# nRF5340.net
KiCad netlist of a schematic drawn in Altium Designer
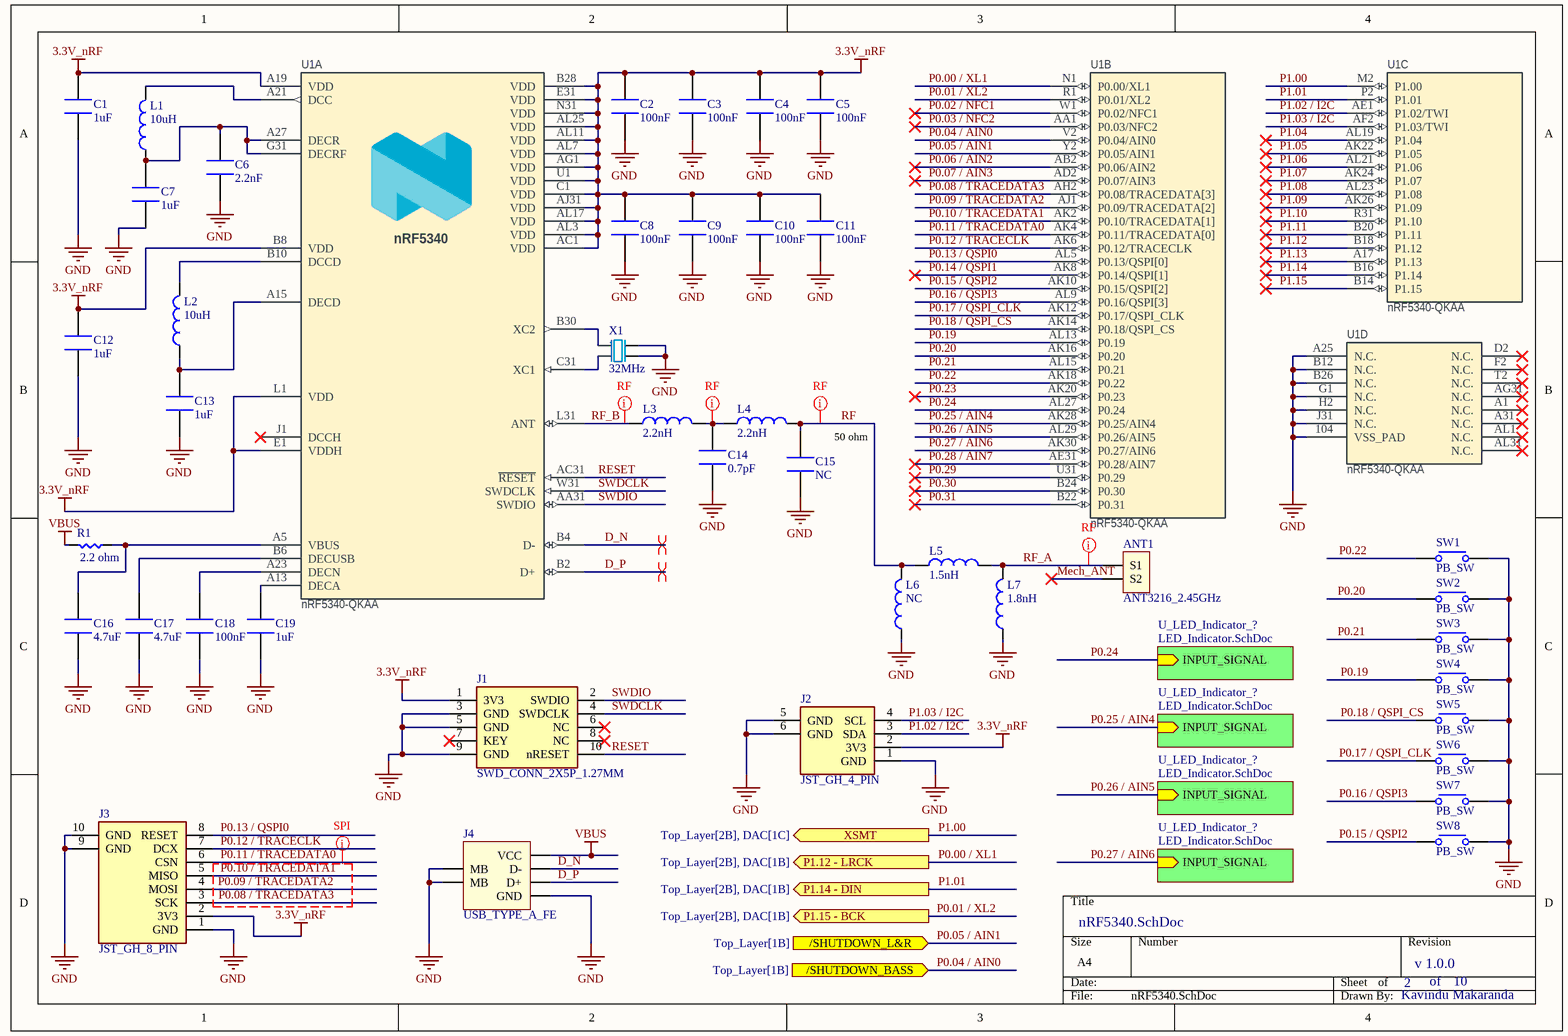
[diagram p0: nRF5340.SchDoc]

(export (version "E")
  (design (tool "Eeschema 10.0.6"))
  (components
    (comp (ref "ANT1")
      (value "ANT3216_2.45GHz")
      (footprint "ANT3216_2.4GHz")
      (libsource (lib "Schlib1") (part "ANT3216_2.45GHz"))
    )
    (comp (ref "C1")
      (value "1uF")
      (footprint "CAPC0402X06N")
      (description "C307427, CL05B105KQ5NQNC, 1uF 6.3V X7R ±10% 0402 Multilayer Ceramic Capacitors MLCC - SMD/SMT ROHS")
      (libsource (lib "Schlib1") (part "CC0402_1uF_X7R"))
    )
    (comp (ref "C2")
      (value "100nF")
      (footprint "CAPC0201X03N")
      (libsource (lib "Schlib1") (part "CC0201_100nF_X7R"))
    )
    (comp (ref "C3")
      (value "100nF")
      (footprint "CAPC0201X03N")
      (libsource (lib "Schlib1") (part "CC0201_100nF_X7R"))
    )
    (comp (ref "C4")
      (value "100nF")
      (footprint "CAPC0201X03N")
      (libsource (lib "Schlib1") (part "CC0201_100nF_X7R"))
    )
    (comp (ref "C5")
      (value "100nF")
      (footprint "CAPC0201X03N")
      (libsource (lib "Schlib1") (part "CC0201_100nF_X7R"))
    )
    (comp (ref "C6")
      (value "2.2nF")
      (footprint "CAPC0201X03N")
      (libsource (lib "Schlib1") (part "CC0201_2.2nF_X7R"))
    )
    (comp (ref "C7")
      (value "1uF")
      (footprint "CAPC0402X06N")
      (description "C307427, CL05B105KQ5NQNC, 1uF 6.3V X7R ±10% 0402 Multilayer Ceramic Capacitors MLCC - SMD/SMT ROHS")
      (libsource (lib "Schlib1") (part "CC0402_1uF_X7R"))
    )
    (comp (ref "C8")
      (value "100nF")
      (footprint "CAPC0201X03N")
      (libsource (lib "Schlib1") (part "CC0201_100nF_X7R"))
    )
    (comp (ref "C9")
      (value "100nF")
      (footprint "CAPC0201X03N")
      (libsource (lib "Schlib1") (part "CC0201_100nF_X7R"))
    )
    (comp (ref "C10")
      (value "100nF")
      (footprint "CAPC0201X03N")
      (libsource (lib "Schlib1") (part "CC0201_100nF_X7R"))
    )
    (comp (ref "C11")
      (value "100nF")
      (footprint "CAPC0201X03N")
      (libsource (lib "Schlib1") (part "CC0201_100nF_X7R"))
    )
    (comp (ref "C12")
      (value "1uF")
      (footprint "CAPC0402X06N")
      (description "C307427, CL05B105KQ5NQNC, 1uF 6.3V X7R ±10% 0402 Multilayer Ceramic Capacitors MLCC - SMD/SMT ROHS")
      (libsource (lib "Schlib1") (part "CC0402_1uF_X7R"))
    )
    (comp (ref "C13")
      (value "1uF")
      (footprint "CAPC0402X06N")
      (description "C307427, CL05B105KQ5NQNC, 1uF 6.3V X7R ±10% 0402 Multilayer Ceramic Capacitors MLCC - SMD/SMT ROHS")
      (libsource (lib "Schlib1") (part "CC0402_1uF_X7R"))
    )
    (comp (ref "C14")
      (value "0.7pF")
      (footprint "CAPC0201X03N")
      (description "C907945, GJM0335C1ER70WB01D, 0.7pF 25V C0G 0201 Multilayer Ceramic Capacitors MLCC - SMD/SMT ROHS")
      (libsource (lib "Schlib1") (part "CC0201_0.7pF_COG"))
    )
    (comp (ref "C15")
      (value "NC")
      (footprint "CAPC0201X03N")
      (description "C907945, GJM0335C1ER70WB01D, 0.7pF 25V C0G 0201 Multilayer Ceramic Capacitors MLCC - SMD/SMT ROHS")
      (libsource (lib "Schlib1") (part "CC0201_0.7pF_COG"))
    )
    (comp (ref "C16")
      (value "4.7uF")
      (footprint "CAP0805X13N")
      (libsource (lib "Schlib1") (part "CC0805_4.7uF_X7R"))
    )
    (comp (ref "C17")
      (value "4.7uF")
      (footprint "CAP0805X13N")
      (libsource (lib "Schlib1") (part "CC0805_4.7uF_X7R"))
    )
    (comp (ref "C18")
      (value "100nF")
      (footprint "CAPC0201X03N")
      (libsource (lib "Schlib1") (part "CC0201_100nF_X7R"))
    )
    (comp (ref "C19")
      (value "1uF")
      (footprint "CAPC0402X06N")
      (description "C307427, CL05B105KQ5NQNC, 1uF 6.3V X7R ±10% 0402 Multilayer Ceramic Capacitors MLCC - SMD/SMT ROHS")
      (libsource (lib "Schlib1") (part "CC0402_1uF_X7R"))
    )
    (comp (ref "J1")
      (value "SWD_CONN_2X5P_1.27MM")
      (footprint "CONN_2X5P_1.27MM - duplicate")
      (libsource (lib "Schlib1") (part "SWD_CONN_2X5P_1.27MM"))
    )
    (comp (ref "J2")
      (value "JST_GH_4_PIN")
      (footprint "JST_GH_4_PIN")
      (libsource (lib "Schlib1") (part "JST_GH_4_PIN"))
    )
    (comp (ref "J3")
      (value "JST_GH_8_PIN")
      (footprint "JST_GH_8_PIN")
      (libsource (lib "Schlib1") (part "JST_GH_8_PIN"))
    )
    (comp (ref "J4")
      (value "USB_TYPE_A_FE")
      (footprint "USB_TYPE_A_FE")
      (libsource (lib "Schlib1") (part "USB_TYPE_A_FE"))
    )
    (comp (ref "L1")
      (value "10uH")
      (footprint "INDC0603X08N")
      (libsource (lib "Schlib1") (part "IN0603_10uH"))
    )
    (comp (ref "L2")
      (value "10uH")
      (footprint "INDC0603X08N")
      (libsource (lib "Schlib1") (part "IN0603_10uH"))
    )
    (comp (ref "L3") (value "2.2nH") (footprint "INDC0201") (libsource (lib "Schlib1") (part "IN0201_2.2nH")))
    (comp (ref "L4") (value "2.2nH") (footprint "INDC0201") (libsource (lib "Schlib1") (part "IN0201_2.2nH")))
    (comp (ref "L5") (value "1.5nH") (footprint "INDC0201") (libsource (lib "Schlib1") (part "IN0201_1.5nH")))
    (comp (ref "L6") (value "NC") (footprint "INDC0201") (libsource (lib "Schlib1") (part "IN0201_1.8nH")))
    (comp (ref "L7") (value "1.8nH") (footprint "INDC0201") (libsource (lib "Schlib1") (part "IN0201_1.8nH")))
    (comp (ref "R1")
      (value "2.2 ohm")
      (footprint "CAPC0201X03N")
      (libsource (lib "Schlib1") (part "REC0201_2.2_THICK"))
    )
    (comp (ref "SW1") (value "PB_SW") (footprint "SW_PB_2") (libsource (lib "Schlib1") (part "SW_SMD_PUSH")))
    (comp (ref "SW2") (value "PB_SW") (footprint "SW_PB_2") (libsource (lib "Schlib1") (part "SW_SMD_PUSH")))
    (comp (ref "SW3") (value "PB_SW") (footprint "SW_PB_2") (libsource (lib "Schlib1") (part "SW_SMD_PUSH")))
    (comp (ref "SW4") (value "PB_SW") (footprint "SW_PB_2") (libsource (lib "Schlib1") (part "SW_SMD_PUSH")))
    (comp (ref "SW5") (value "PB_SW") (footprint "SW_PB_2") (libsource (lib "Schlib1") (part "SW_SMD_PUSH")))
    (comp (ref "SW6") (value "PB_SW") (footprint "SW_PB_2") (libsource (lib "Schlib1") (part "SW_SMD_PUSH")))
    (comp (ref "SW7") (value "PB_SW") (footprint "SW_PB_2") (libsource (lib "Schlib1") (part "SW_SMD_PUSH")))
    (comp (ref "SW8") (value "PB_SW") (footprint "SW_PB_2") (libsource (lib "Schlib1") (part "SW_SMD_PUSH")))
    (comp (ref "U1")
      (value "nRF5340-QKAA")
      (footprint "AQFN40P700X700X85_HS-99N")
      (description "Multi-protocol Bluetooth Low Energy, IEEE 802.15.4, ANT and 2.4GHz proprietary system-on-chip")
      (libsource (lib "nRF5340_qkaa_config4") (part "nRF5340-QKAA"))
    )
    (comp (ref "X1")
      (value "32MHz")
      (footprint "CRYOSC_3.2X2.5M")
      (libsource (lib "Schlib1") (part "SMD3225_4P_32MHz_OSC"))
    )
  )
  (nets
    (net (code "1") (name "/D_N") (class "Default")
      (node (ref "J4") (pin "2") (pinfunction "D-_2") (pintype "passive"))
      (node (ref "U1") (pin "B4") (pinfunction "D-_B4") (pintype "bidirectional"))
    )
    (net (code "2") (name "/D_P") (class "Default")
      (node (ref "J4") (pin "3") (pinfunction "D+_3") (pintype "passive"))
      (node (ref "U1") (pin "B2") (pinfunction "D+_B2") (pintype "bidirectional"))
    )
    (net (code "3") (name "/Mech_ANT") (class "Default")
      (node (ref "ANT1") (pin "2") (pinfunction "S2_2") (pintype "passive+no_connect"))
    )
    (net (code "4") (name "/P0.00 {slash} XL1") (class "Default")
      (node (ref "U1") (pin "N1") (pinfunction "P0.00/XL1_N1") (pintype "bidirectional"))
    )
    (net (code "5") (name "/P0.01 {slash} XL2") (class "Default")
      (node (ref "U1") (pin "R1") (pinfunction "P0.01/XL2_R1") (pintype "bidirectional"))
    )
    (net (code "6") (name "/P0.02 {slash} NFC1") (class "Default")
      (node (ref "U1") (pin "W1") (pinfunction "P0.02/NFC1_W1") (pintype "bidirectional+no_connect"))
    )
    (net (code "7") (name "/P0.03 {slash} NFC2") (class "Default")
      (node (ref "U1") (pin "AA1") (pinfunction "P0.03/NFC2_AA1") (pintype "bidirectional+no_connect"))
    )
    (net (code "8") (name "/P0.04 {slash} AIN0") (class "Default")
      (node (ref "U1") (pin "V2") (pinfunction "P0.04/AIN0_V2") (pintype "bidirectional"))
    )
    (net (code "9") (name "/P0.05 {slash} AIN1") (class "Default")
      (node (ref "U1") (pin "Y2") (pinfunction "P0.05/AIN1_Y2") (pintype "bidirectional"))
    )
    (net (code "10") (name "/P0.06 {slash} AIN2") (class "Default")
      (node (ref "U1") (pin "AB2") (pinfunction "P0.06/AIN2_AB2") (pintype "bidirectional+no_connect"))
    )
    (net (code "11") (name "/P0.07 {slash} AIN3") (class "Default")
      (node (ref "U1") (pin "AD2") (pinfunction "P0.07/AIN3_AD2") (pintype "bidirectional+no_connect"))
    )
    (net (code "12") (name "/P0.08 {slash} TRACEDATA3") (class "Default")
      (node (ref "J3") (pin "3") (pinfunction "SCK_3") (pintype "passive"))
      (node (ref "U1") (pin "AH2") (pinfunction "P0.08/TRACEDATA[3]_AH2") (pintype "bidirectional"))
    )
    (net (code "13") (name "/P0.09 {slash} TRACEDATA2") (class "Default")
      (node (ref "J3") (pin "4") (pinfunction "MOSI_4") (pintype "passive"))
      (node (ref "U1") (pin "AJ1") (pinfunction "P0.09/TRACEDATA[2]_AJ1") (pintype "bidirectional"))
    )
    (net (code "14") (name "/P0.10 {slash} TRACEDATA1") (class "Default")
      (node (ref "J3") (pin "5") (pinfunction "MISO_5") (pintype "passive"))
      (node (ref "U1") (pin "AK2") (pinfunction "P0.10/TRACEDATA[1]_AK2") (pintype "bidirectional"))
    )
    (net (code "15") (name "/P0.11 {slash} TRACEDATA0") (class "Default")
      (node (ref "J3") (pin "6") (pinfunction "CSN_6") (pintype "passive"))
      (node (ref "U1") (pin "AK4") (pinfunction "P0.11/TRACEDATA[0]_AK4") (pintype "bidirectional"))
    )
    (net (code "16") (name "/P0.12 {slash} TRACECLK") (class "Default")
      (node (ref "J3") (pin "7") (pinfunction "DCX_7") (pintype "passive"))
      (node (ref "U1") (pin "AK6") (pinfunction "P0.12/TRACECLK_AK6") (pintype "bidirectional"))
    )
    (net (code "17") (name "/P0.13 {slash} QSPI0") (class "Default")
      (node (ref "J3") (pin "8") (pinfunction "RESET_8") (pintype "passive"))
      (node (ref "U1") (pin "AL5") (pinfunction "P0.13/QSPI[0]_AL5") (pintype "bidirectional"))
    )
    (net (code "18") (name "/P0.14 {slash} QSPI1") (class "Default")
      (node (ref "U1") (pin "AK8") (pinfunction "P0.14/QSPI[1]_AK8") (pintype "bidirectional+no_connect"))
    )
    (net (code "19") (name "/P0.15 {slash} QSPI2") (class "Default")
      (node (ref "SW8") (pin "1") (pinfunction "1_1") (pintype "passive"))
      (node (ref "U1") (pin "AK10") (pinfunction "P0.15/QSPI[2]_AK10") (pintype "bidirectional"))
    )
    (net (code "20") (name "/P0.16 {slash} QSPI3") (class "Default")
      (node (ref "SW7") (pin "1") (pinfunction "1_1") (pintype "passive"))
      (node (ref "U1") (pin "AL9") (pinfunction "P0.16/QSPI[3]_AL9") (pintype "bidirectional"))
    )
    (net (code "21") (name "/P0.17 {slash} QSPI_CLK") (class "Default")
      (node (ref "SW6") (pin "1") (pinfunction "1_1") (pintype "passive"))
      (node (ref "U1") (pin "AK12") (pinfunction "P0.17/QSPI_CLK_AK12") (pintype "bidirectional"))
    )
    (net (code "22") (name "/P0.18 {slash} QSPI_CS") (class "Default")
      (node (ref "SW5") (pin "1") (pinfunction "1_1") (pintype "passive"))
      (node (ref "U1") (pin "AK14") (pinfunction "P0.18/QSPI_CS_AK14") (pintype "bidirectional"))
    )
    (net (code "23") (name "/P0.19") (class "Default")
      (node (ref "SW4") (pin "1") (pinfunction "1_1") (pintype "passive"))
      (node (ref "U1") (pin "AL13") (pinfunction "P0.19_AL13") (pintype "bidirectional"))
    )
    (net (code "24") (name "/P0.20") (class "Default")
      (node (ref "SW2") (pin "1") (pinfunction "1_1") (pintype "passive"))
      (node (ref "U1") (pin "AK16") (pinfunction "P0.20_AK16") (pintype "bidirectional"))
    )
    (net (code "25") (name "/P0.21") (class "Default")
      (node (ref "SW3") (pin "1") (pinfunction "1_1") (pintype "passive"))
      (node (ref "U1") (pin "AL15") (pinfunction "P0.21_AL15") (pintype "bidirectional"))
    )
    (net (code "26") (name "/P0.22") (class "Default")
      (node (ref "SW1") (pin "1") (pinfunction "1_1") (pintype "passive"))
      (node (ref "U1") (pin "AK18") (pinfunction "P0.22_AK18") (pintype "bidirectional"))
    )
    (net (code "27") (name "/P0.23") (class "Default")
      (node (ref "U1") (pin "AK20") (pinfunction "P0.23_AK20") (pintype "bidirectional+no_connect"))
    )
    (net (code "28") (name "/P0.24") (class "Default")
      (node (ref "U1") (pin "AL27") (pinfunction "P0.24_AL27") (pintype "bidirectional"))
    )
    (net (code "29") (name "/P0.25 {slash} AIN4") (class "Default")
      (node (ref "U1") (pin "AK28") (pinfunction "P0.25/AIN4_AK28") (pintype "bidirectional"))
    )
    (net (code "30") (name "/P0.26 {slash} AIN5") (class "Default")
      (node (ref "U1") (pin "AL29") (pinfunction "P0.26/AIN5_AL29") (pintype "bidirectional"))
    )
    (net (code "31") (name "/P0.27 {slash} AIN6") (class "Default")
      (node (ref "U1") (pin "AK30") (pinfunction "P0.27/AIN6_AK30") (pintype "bidirectional"))
    )
    (net (code "32") (name "/P0.28 {slash} AIN7") (class "Default")
      (node (ref "U1") (pin "AE31") (pinfunction "P0.28/AIN7_AE31") (pintype "bidirectional+no_connect"))
    )
    (net (code "33") (name "/P0.29") (class "Default")
      (node (ref "U1") (pin "U31") (pinfunction "P0.29_U31") (pintype "bidirectional+no_connect"))
    )
    (net (code "34") (name "/P0.30") (class "Default")
      (node (ref "U1") (pin "B24") (pinfunction "P0.30_B24") (pintype "bidirectional+no_connect"))
    )
    (net (code "35") (name "/P0.31") (class "Default")
      (node (ref "U1") (pin "B22") (pinfunction "P0.31_B22") (pintype "bidirectional+no_connect"))
    )
    (net (code "36") (name "/P1.00") (class "Default")
      (node (ref "U1") (pin "M2") (pinfunction "P1.00_M2") (pintype "bidirectional"))
    )
    (net (code "37") (name "/P1.01") (class "Default")
      (node (ref "U1") (pin "P2") (pinfunction "P1.01_P2") (pintype "bidirectional"))
    )
    (net (code "38") (name "/P1.02 {slash} I2C") (class "Default")
      (node (ref "J2") (pin "3") (pinfunction "SDA_3") (pintype "passive"))
      (node (ref "U1") (pin "AE1") (pinfunction "P1.02/TWI_AE1") (pintype "bidirectional"))
    )
    (net (code "39") (name "/P1.03 {slash} I2C") (class "Default")
      (node (ref "J2") (pin "4") (pinfunction "SCL_4") (pintype "passive"))
      (node (ref "U1") (pin "AF2") (pinfunction "P1.03/TWI_AF2") (pintype "bidirectional"))
    )
    (net (code "40") (name "/P1.04") (class "Default")
      (node (ref "U1") (pin "AL19") (pinfunction "P1.04_AL19") (pintype "bidirectional+no_connect"))
    )
    (net (code "41") (name "/P1.05") (class "Default")
      (node (ref "U1") (pin "AK22") (pinfunction "P1.05_AK22") (pintype "bidirectional+no_connect"))
    )
    (net (code "42") (name "/P1.06") (class "Default")
      (node (ref "U1") (pin "AL21") (pinfunction "P1.06_AL21") (pintype "bidirectional+no_connect"))
    )
    (net (code "43") (name "/P1.07") (class "Default")
      (node (ref "U1") (pin "AK24") (pinfunction "P1.07_AK24") (pintype "bidirectional+no_connect"))
    )
    (net (code "44") (name "/P1.08") (class "Default")
      (node (ref "U1") (pin "AL23") (pinfunction "P1.08_AL23") (pintype "bidirectional+no_connect"))
    )
    (net (code "45") (name "/P1.09") (class "Default")
      (node (ref "U1") (pin "AK26") (pinfunction "P1.09_AK26") (pintype "bidirectional+no_connect"))
    )
    (net (code "46") (name "/P1.10") (class "Default")
      (node (ref "U1") (pin "R31") (pinfunction "P1.10_R31") (pintype "bidirectional+no_connect"))
    )
    (net (code "47") (name "/P1.11") (class "Default")
      (node (ref "U1") (pin "B20") (pinfunction "P1.11_B20") (pintype "bidirectional+no_connect"))
    )
    (net (code "48") (name "/P1.12") (class "Default")
      (node (ref "U1") (pin "B18") (pinfunction "P1.12_B18") (pintype "bidirectional+no_connect"))
    )
    (net (code "49") (name "/P1.13") (class "Default")
      (node (ref "U1") (pin "A17") (pinfunction "P1.13_A17") (pintype "bidirectional+no_connect"))
    )
    (net (code "50") (name "/P1.14") (class "Default")
      (node (ref "U1") (pin "B16") (pinfunction "P1.14_B16") (pintype "bidirectional+no_connect"))
    )
    (net (code "51") (name "/P1.15") (class "Default")
      (node (ref "U1") (pin "B14") (pinfunction "P1.15_B14") (pintype "bidirectional+no_connect"))
    )
    (net (code "52") (name "/RESET") (class "Default")
      (node (ref "J1") (pin "10") (pinfunction "nRESET_10") (pintype "passive"))
      (node (ref "U1") (pin "AC31") (pinfunction "~{RESET}_AC31") (pintype "input"))
    )
    (net (code "53") (name "/RF") (class "Default")
      (node (ref "C15") (pin "1") (pinfunction "1_1") (pintype "passive"))
      (node (ref "L4") (pin "2") (pinfunction "2_2") (pintype "passive"))
      (node (ref "L5") (pin "1") (pinfunction "1_1") (pintype "passive"))
      (node (ref "L6") (pin "2") (pinfunction "2_2") (pintype "passive"))
    )
    (net (code "54") (name "/RF_A") (class "Default")
      (node (ref "ANT1") (pin "1") (pinfunction "S1_1") (pintype "passive"))
      (node (ref "L5") (pin "2") (pinfunction "2_2") (pintype "passive"))
      (node (ref "L7") (pin "2") (pinfunction "2_2") (pintype "passive"))
    )
    (net (code "55") (name "/RF_B") (class "Default")
      (node (ref "L3") (pin "1") (pinfunction "1_1") (pintype "passive"))
      (node (ref "U1") (pin "L31") (pinfunction "ANT_L31") (pintype "bidirectional"))
    )
    (net (code "56") (name "/SWDCLK") (class "Default")
      (node (ref "J1") (pin "4") (pinfunction "SWDCLK_4") (pintype "passive"))
      (node (ref "U1") (pin "W31") (pinfunction "SWDCLK_W31") (pintype "input"))
    )
    (net (code "57") (name "/SWDIO") (class "Default")
      (node (ref "J1") (pin "2") (pinfunction "SWDIO_2") (pintype "passive"))
      (node (ref "U1") (pin "AA31") (pinfunction "SWDIO_AA31") (pintype "bidirectional"))
    )
    (net (code "58") (name "3.3V_nRF") (class "Default")
      (node (ref "C1") (pin "2") (pinfunction "2_2") (pintype "passive"))
      (node (ref "C10") (pin "2") (pinfunction "2_2") (pintype "passive"))
      (node (ref "C11") (pin "2") (pinfunction "2_2") (pintype "passive"))
      (node (ref "C12") (pin "2") (pinfunction "2_2") (pintype "passive"))
      (node (ref "C2") (pin "2") (pinfunction "2_2") (pintype "passive"))
      (node (ref "C3") (pin "2") (pinfunction "2_2") (pintype "passive"))
      (node (ref "C4") (pin "2") (pinfunction "2_2") (pintype "passive"))
      (node (ref "C5") (pin "2") (pinfunction "2_2") (pintype "passive"))
      (node (ref "C8") (pin "2") (pinfunction "2_2") (pintype "passive"))
      (node (ref "C9") (pin "2") (pinfunction "2_2") (pintype "passive"))
      (node (ref "J1") (pin "1") (pinfunction "3V3_1") (pintype "passive"))
      (node (ref "J2") (pin "2") (pinfunction "3V3_2") (pintype "passive"))
      (node (ref "J3") (pin "2") (pinfunction "3V3_2") (pintype "passive"))
      (node (ref "U1") (pin "A19") (pinfunction "VDD_A19") (pintype "power_in"))
      (node (ref "U1") (pin "AC1") (pinfunction "VDD_AC1") (pintype "power_in"))
      (node (ref "U1") (pin "AG1") (pinfunction "VDD_AG1") (pintype "power_in"))
      (node (ref "U1") (pin "AJ31") (pinfunction "VDD_AJ31") (pintype "power_in"))
      (node (ref "U1") (pin "AL11") (pinfunction "VDD_AL11") (pintype "power_in"))
      (node (ref "U1") (pin "AL17") (pinfunction "VDD_AL17") (pintype "power_in"))
      (node (ref "U1") (pin "AL25") (pinfunction "VDD_AL25") (pintype "power_in"))
      (node (ref "U1") (pin "AL3") (pinfunction "VDD_AL3") (pintype "power_in"))
      (node (ref "U1") (pin "AL7") (pinfunction "VDD_AL7") (pintype "power_in"))
      (node (ref "U1") (pin "B28") (pinfunction "VDD_B28") (pintype "power_in"))
      (node (ref "U1") (pin "B8") (pinfunction "VDD_B8") (pintype "power_in"))
      (node (ref "U1") (pin "C1") (pinfunction "VDD_C1") (pintype "power_in"))
      (node (ref "U1") (pin "E1") (pinfunction "VDDH_E1") (pintype "power_in"))
      (node (ref "U1") (pin "E31") (pinfunction "VDD_E31") (pintype "power_in"))
      (node (ref "U1") (pin "L1") (pinfunction "VDD_L1") (pintype "power_in"))
      (node (ref "U1") (pin "N31") (pinfunction "VDD_N31") (pintype "power_in"))
      (node (ref "U1") (pin "U1") (pinfunction "VDD_U1") (pintype "power_in"))
    )
    (net (code "59") (name "GND") (class "Default")
      (node (ref "C1") (pin "1") (pinfunction "1_1") (pintype "passive"))
      (node (ref "C10") (pin "1") (pinfunction "1_1") (pintype "passive"))
      (node (ref "C11") (pin "1") (pinfunction "1_1") (pintype "passive"))
      (node (ref "C12") (pin "1") (pinfunction "1_1") (pintype "passive"))
      (node (ref "C13") (pin "1") (pinfunction "1_1") (pintype "passive"))
      (node (ref "C14") (pin "2") (pinfunction "2_2") (pintype "passive"))
      (node (ref "C15") (pin "2") (pinfunction "2_2") (pintype "passive"))
      (node (ref "C16") (pin "1") (pinfunction "1_1") (pintype "passive"))
      (node (ref "C17") (pin "1") (pinfunction "1_1") (pintype "passive"))
      (node (ref "C18") (pin "1") (pinfunction "1_1") (pintype "passive"))
      (node (ref "C19") (pin "1") (pinfunction "1_1") (pintype "passive"))
      (node (ref "C2") (pin "1") (pinfunction "1_1") (pintype "passive"))
      (node (ref "C3") (pin "1") (pinfunction "1_1") (pintype "passive"))
      (node (ref "C4") (pin "1") (pinfunction "1_1") (pintype "passive"))
      (node (ref "C5") (pin "1") (pinfunction "1_1") (pintype "passive"))
      (node (ref "C6") (pin "1") (pinfunction "1_1") (pintype "passive"))
      (node (ref "C7") (pin "1") (pinfunction "1_1") (pintype "passive"))
      (node (ref "C8") (pin "1") (pinfunction "1_1") (pintype "passive"))
      (node (ref "C9") (pin "1") (pinfunction "1_1") (pintype "passive"))
      (node (ref "J1") (pin "3") (pinfunction "GND_3") (pintype "passive"))
      (node (ref "J1") (pin "5") (pinfunction "GND_5") (pintype "passive"))
      (node (ref "J1") (pin "9") (pinfunction "GND_9") (pintype "passive"))
      (node (ref "J2") (pin "1") (pinfunction "GND_1") (pintype "passive"))
      (node (ref "J2") (pin "5") (pinfunction "GND_5") (pintype "passive"))
      (node (ref "J2") (pin "6") (pinfunction "GND_6") (pintype "passive"))
      (node (ref "J3") (pin "1") (pinfunction "GND_1") (pintype "passive"))
      (node (ref "J3") (pin "10") (pinfunction "GND_10") (pintype "passive"))
      (node (ref "J3") (pin "9") (pinfunction "GND_9") (pintype "passive"))
      (node (ref "J4") (pin "4") (pinfunction "GND_4") (pintype "passive"))
      (node (ref "J4") (pin "5") (pinfunction "MB_5") (pintype "passive"))
      (node (ref "J4") (pin "6") (pinfunction "MB_6") (pintype "passive"))
      (node (ref "L6") (pin "1") (pinfunction "1_1") (pintype "passive"))
      (node (ref "L7") (pin "1") (pinfunction "1_1") (pintype "passive"))
      (node (ref "SW1") (pin "2") (pinfunction "2_2") (pintype "passive"))
      (node (ref "SW2") (pin "2") (pinfunction "2_2") (pintype "passive"))
      (node (ref "SW3") (pin "2") (pinfunction "2_2") (pintype "passive"))
      (node (ref "SW4") (pin "2") (pinfunction "2_2") (pintype "passive"))
      (node (ref "SW5") (pin "2") (pinfunction "2_2") (pintype "passive"))
      (node (ref "SW6") (pin "2") (pinfunction "2_2") (pintype "passive"))
      (node (ref "SW7") (pin "2") (pinfunction "2_2") (pintype "passive"))
      (node (ref "SW8") (pin "2") (pinfunction "2_2") (pintype "passive"))
      (node (ref "U1") (pin "104") (pinfunction "VSS_PAD_104") (pintype "power_in"))
      (node (ref "U1") (pin "A25") (pinfunction "N.C._A25") (pintype "passive"))
      (node (ref "U1") (pin "B12") (pinfunction "N.C._B12") (pintype "passive"))
      (node (ref "U1") (pin "B26") (pinfunction "N.C._B26") (pintype "passive"))
      (node (ref "U1") (pin "G1") (pinfunction "N.C._G1") (pintype "passive"))
      (node (ref "U1") (pin "H2") (pinfunction "N.C._H2") (pintype "passive"))
      (node (ref "U1") (pin "J31") (pinfunction "N.C._J31") (pintype "passive"))
      (node (ref "X1") (pin "2") (pinfunction "GND1_2") (pintype "passive"))
      (node (ref "X1") (pin "4") (pinfunction "GND2_4") (pintype "passive"))
    )
    (net (code "60") (name "Net-(C14-Pad1)") (class "Default")
      (node (ref "C14") (pin "1") (pinfunction "1_1") (pintype "passive"))
      (node (ref "L3") (pin "2") (pinfunction "2_2") (pintype "passive"))
      (node (ref "L4") (pin "1") (pinfunction "1_1") (pintype "passive"))
    )
    (net (code "61") (name "Net-(U1A-DCC)") (class "Default")
      (node (ref "L1") (pin "2") (pinfunction "2_2") (pintype "passive"))
      (node (ref "U1") (pin "A21") (pinfunction "DCC_A21") (pintype "output"))
    )
    (net (code "62") (name "Net-(U1A-DCCD)") (class "Default")
      (node (ref "L2") (pin "2") (pinfunction "2_2") (pintype "passive"))
      (node (ref "U1") (pin "B10") (pinfunction "DCCD_B10") (pintype "power_in"))
    )
    (net (code "63") (name "Net-(U1A-DECA)") (class "Default")
      (node (ref "C19") (pin "2") (pinfunction "2_2") (pintype "passive"))
      (node (ref "U1") (pin "A13") (pinfunction "DECA_A13") (pintype "power_in"))
    )
    (net (code "64") (name "Net-(U1A-DECD)") (class "Default")
      (node (ref "C13") (pin "2") (pinfunction "2_2") (pintype "passive"))
      (node (ref "L2") (pin "1") (pinfunction "1_1") (pintype "passive"))
      (node (ref "U1") (pin "A15") (pinfunction "DECD_A15") (pintype "power_in"))
    )
    (net (code "65") (name "Net-(U1A-DECN)") (class "Default")
      (node (ref "C18") (pin "2") (pinfunction "2_2") (pintype "passive"))
      (node (ref "U1") (pin "A23") (pinfunction "DECN_A23") (pintype "power_in"))
    )
    (net (code "66") (name "Net-(U1A-DECR)") (class "Default")
      (node (ref "C6") (pin "2") (pinfunction "2_2") (pintype "passive"))
      (node (ref "C7") (pin "2") (pinfunction "2_2") (pintype "passive"))
      (node (ref "L1") (pin "1") (pinfunction "1_1") (pintype "passive"))
      (node (ref "U1") (pin "A27") (pinfunction "DECR_A27") (pintype "power_in"))
      (node (ref "U1") (pin "G31") (pinfunction "DECRF_G31") (pintype "power_in"))
    )
    (net (code "67") (name "Net-(U1A-DECUSB)") (class "Default")
      (node (ref "C17") (pin "2") (pinfunction "2_2") (pintype "passive"))
      (node (ref "U1") (pin "B6") (pinfunction "DECUSB_B6") (pintype "power_in"))
    )
    (net (code "68") (name "Net-(U1A-VBUS)") (class "Default")
      (node (ref "C16") (pin "2") (pinfunction "2_2") (pintype "passive"))
      (node (ref "R1") (pin "1") (pinfunction "1_1") (pintype "passive"))
      (node (ref "U1") (pin "A5") (pinfunction "VBUS_A5") (pintype "power_in"))
    )
    (net (code "69") (name "Net-(U1A-XC1)") (class "Default")
      (node (ref "U1") (pin "C31") (pinfunction "XC1_C31") (pintype "input"))
      (node (ref "X1") (pin "3") (pinfunction "CLK2_3") (pintype "passive"))
    )
    (net (code "70") (name "Net-(U1A-XC2)") (class "Default")
      (node (ref "U1") (pin "B30") (pinfunction "XC2_B30") (pintype "output"))
      (node (ref "X1") (pin "1") (pinfunction "CLK1_1") (pintype "passive"))
    )
    (net (code "71") (name "VBUS") (class "Default")
      (node (ref "J4") (pin "1") (pinfunction "VCC_1") (pintype "passive"))
      (node (ref "R1") (pin "2") (pinfunction "2_2") (pintype "passive"))
    )
    (net (code "72") (name "unconnected-(J1-KEY-Pad7)") (class "Default")
      (node (ref "J1") (pin "7") (pinfunction "KEY_7") (pintype "passive+no_connect"))
    )
    (net (code "73") (name "unconnected-(J1-NC-Pad6)") (class "Default")
      (node (ref "J1") (pin "6") (pinfunction "NC_6") (pintype "passive+no_connect"))
    )
    (net (code "74") (name "unconnected-(J1-NC-Pad8)") (class "Default")
      (node (ref "J1") (pin "8") (pinfunction "NC_8") (pintype "passive+no_connect"))
    )
    (net (code "75") (name "unconnected-(U1A-DCCH-PadJ1)") (class "Default")
      (node (ref "U1") (pin "J1") (pinfunction "DCCH_J1") (pintype "power_in+no_connect"))
    )
    (net (code "76") (name "unconnected-(U1D-N.C.-PadA1)") (class "Default")
      (node (ref "U1") (pin "A1") (pinfunction "N.C._A1") (pintype "passive+no_connect"))
    )
    (net (code "77") (name "unconnected-(U1D-N.C.-PadA31)") (class "Default")
      (node (ref "U1") (pin "A31") (pinfunction "N.C._A31") (pintype "passive+no_connect"))
    )
    (net (code "78") (name "unconnected-(U1D-N.C.-PadAG31)") (class "Default")
      (node (ref "U1") (pin "AG31") (pinfunction "N.C._AG31") (pintype "passive+no_connect"))
    )
    (net (code "79") (name "unconnected-(U1D-N.C.-PadAL1)") (class "Default")
      (node (ref "U1") (pin "AL1") (pinfunction "N.C._AL1") (pintype "passive+no_connect"))
    )
    (net (code "80") (name "unconnected-(U1D-N.C.-PadAL31)") (class "Default")
      (node (ref "U1") (pin "AL31") (pinfunction "N.C._AL31") (pintype "passive+no_connect"))
    )
    (net (code "81") (name "unconnected-(U1D-N.C.-PadD2)") (class "Default")
      (node (ref "U1") (pin "D2") (pinfunction "N.C._D2") (pintype "passive+no_connect"))
    )
    (net (code "82") (name "unconnected-(U1D-N.C.-PadF2)") (class "Default")
      (node (ref "U1") (pin "F2") (pinfunction "N.C._F2") (pintype "passive+no_connect"))
    )
    (net (code "83") (name "unconnected-(U1D-N.C.-PadT2)") (class "Default")
      (node (ref "U1") (pin "T2") (pinfunction "N.C._T2") (pintype "passive+no_connect"))
    )
  )
)
